# main_4.net
KiCad netlist of a schematic drawn in Altium Designer
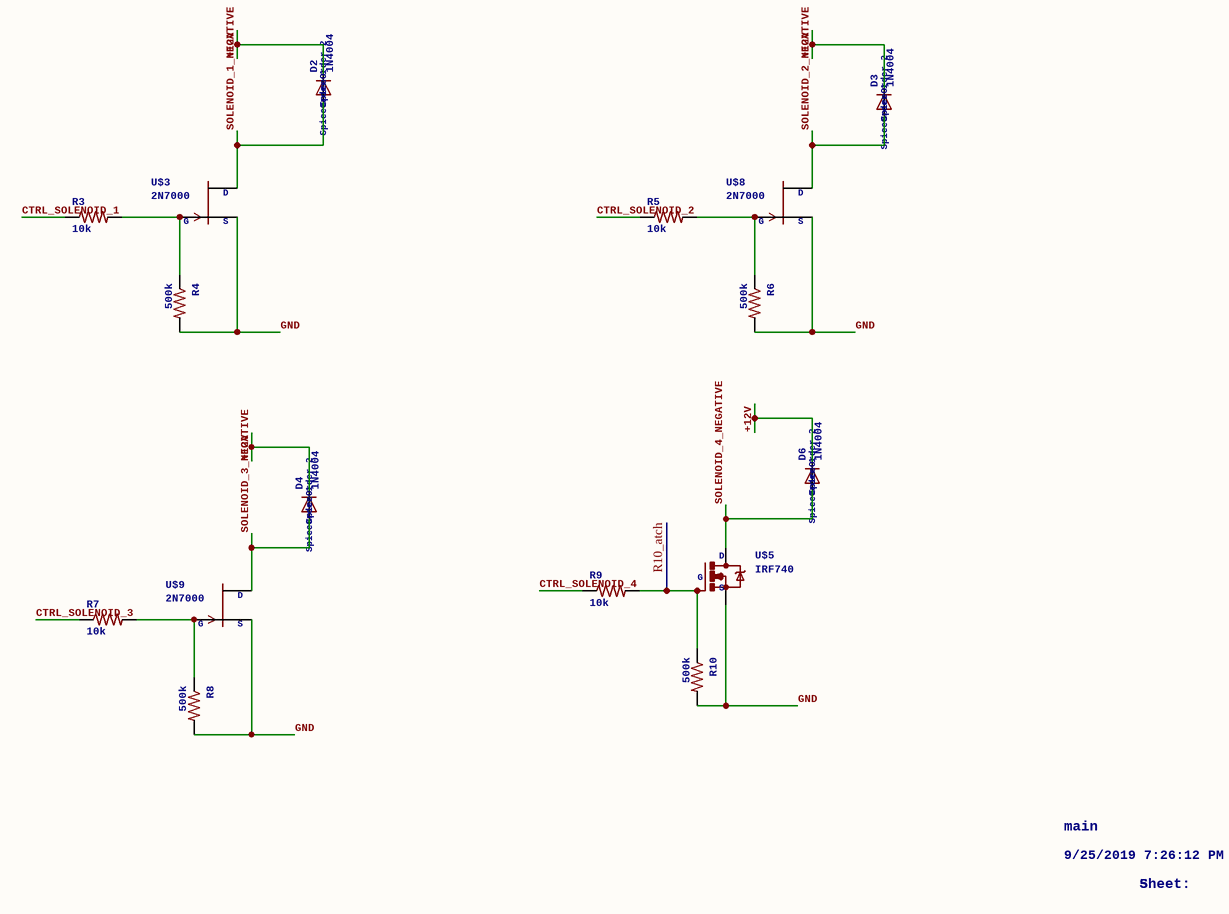
[diagram p0: main_4.SchDoc]

(export (version "E")
  (design (tool "Eeschema 10.0.6"))
  (components
    (comp (ref "D2")
      (value "1N4004")
      (footprint "DO41-10")
      (description "DIODEgeneral purpose rectifier, 1 A")
      (fields (field (name "SPICEORDER1") "SpiceOrder 1") (field (name "SPICEORDER2") "SpiceOrder 2"))
      (libsource (lib "diode") (part "1N4004"))
    )
    (comp (ref "D3")
      (value "1N4004")
      (footprint "DO41-10")
      (description "DIODEgeneral purpose rectifier, 1 A")
      (fields (field (name "SPICEORDER1") "SpiceOrder 1") (field (name "SPICEORDER2") "SpiceOrder 2"))
      (libsource (lib "diode") (part "1N4004"))
    )
    (comp (ref "D4")
      (value "1N4004")
      (footprint "DO41-10")
      (description "DIODEgeneral purpose rectifier, 1 A")
      (fields (field (name "SPICEORDER1") "SpiceOrder 1") (field (name "SPICEORDER2") "SpiceOrder 2"))
      (libsource (lib "diode") (part "1N4004"))
    )
    (comp (ref "D6")
      (value "1N4004")
      (footprint "DO41-10")
      (description "DIODEgeneral purpose rectifier, 1 A")
      (fields (field (name "SPICEORDER1") "SpiceOrder 1") (field (name "SPICEORDER2") "SpiceOrder 2"))
      (libsource (lib "diode") (part "1N4004"))
    )
    (comp (ref "R3")
      (value "10k")
      (footprint "R0805")
      (description "RESISTOR, American symbol")
      (libsource (lib "rcl") (part "R-US_R0805"))
    )
    (comp (ref "R4")
      (value "500k")
      (footprint "R0805")
      (description "RESISTOR, American symbol")
      (libsource (lib "rcl") (part "R-US_R0805"))
    )
    (comp (ref "R5")
      (value "10k")
      (footprint "R0805")
      (description "RESISTOR, American symbol")
      (libsource (lib "rcl") (part "R-US_R0805"))
    )
    (comp (ref "R6")
      (value "500k")
      (footprint "R0805")
      (description "RESISTOR, American symbol")
      (libsource (lib "rcl") (part "R-US_R0805"))
    )
    (comp (ref "R7")
      (value "10k")
      (footprint "R0805")
      (description "RESISTOR, American symbol")
      (libsource (lib "rcl") (part "R-US_R0805"))
    )
    (comp (ref "R8")
      (value "500k")
      (footprint "R0805")
      (description "RESISTOR, American symbol")
      (libsource (lib "rcl") (part "R-US_R0805"))
    )
    (comp (ref "R9")
      (value "10k")
      (footprint "R0805")
      (description "RESISTOR, American symbol")
      (libsource (lib "rcl") (part "R-US_R0805"))
    )
    (comp (ref "R10")
      (value "500k")
      (footprint "R0805")
      (description "RESISTOR, American symbol")
      (libsource (lib "rcl") (part "R-US_R0805"))
    )
    (comp (ref "U$3")
      (value "2N7000")
      (footprint "SOT23")
      (fields
        (field (name "D") "D")
        (field (name "S") "S")
        (field (name "G") "G")
        (field (name "LIBRARYNAME") "transistor-fet-extra")
      )
      (libsource (lib "transistor-fet-extra") (part "2N7000"))
    )
    (comp (ref "U$5")
      (value "IRF740")
      (footprint "TO220BV")
      (description "N-CHANNEL MOS FET")
      (fields (field (name "D") "D") (field (name "S") "S") (field (name "G") "G"))
      (libsource (lib "transistor-power") (part "IRF740"))
    )
    (comp (ref "U$8")
      (value "2N7000")
      (footprint "SOT23")
      (fields
        (field (name "D") "D")
        (field (name "S") "S")
        (field (name "G") "G")
        (field (name "LIBRARYNAME") "transistor-fet-extra")
      )
      (libsource (lib "transistor-fet-extra") (part "2N7000"))
    )
    (comp (ref "U$9")
      (value "2N7000")
      (footprint "SOT23")
      (fields
        (field (name "D") "D")
        (field (name "S") "S")
        (field (name "G") "G")
        (field (name "LIBRARYNAME") "transistor-fet-extra")
      )
      (libsource (lib "transistor-fet-extra") (part "2N7000"))
    )
  )
  (nets
    (net (code "1") (name "/+12V") (class "Default")
      (node (ref "D2") (pin "C") (pinfunction "C_C") (pintype "passive"))
      (node (ref "D3") (pin "C") (pinfunction "C_C") (pintype "passive"))
      (node (ref "D4") (pin "C") (pinfunction "C_C") (pintype "passive"))
      (node (ref "D6") (pin "C") (pinfunction "C_C") (pintype "passive"))
    )
    (net (code "2") (name "/CTRL_SOLENOID_1") (class "Default")
      (node (ref "R3") (pin "1") (pinfunction "1_1") (pintype "passive"))
    )
    (net (code "3") (name "/CTRL_SOLENOID_2") (class "Default")
      (node (ref "R5") (pin "1") (pinfunction "1_1") (pintype "passive"))
    )
    (net (code "4") (name "/CTRL_SOLENOID_3") (class "Default")
      (node (ref "R7") (pin "1") (pinfunction "1_1") (pintype "passive"))
    )
    (net (code "5") (name "/CTRL_SOLENOID_4") (class "Default")
      (node (ref "R9") (pin "1") (pinfunction "1_1") (pintype "passive"))
    )
    (net (code "6") (name "/GND") (class "Default")
      (node (ref "R10") (pin "2") (pinfunction "2_2") (pintype "passive"))
      (node (ref "R4") (pin "2") (pinfunction "2_2") (pintype "passive"))
      (node (ref "R6") (pin "2") (pinfunction "2_2") (pintype "passive"))
      (node (ref "R8") (pin "2") (pinfunction "2_2") (pintype "passive"))
      (node (ref "U$3") (pin "2") (pinfunction "S_2") (pintype "passive"))
      (node (ref "U$5") (pin "S") (pinfunction "S_S") (pintype "passive"))
      (node (ref "U$8") (pin "2") (pinfunction "S_2") (pintype "passive"))
      (node (ref "U$9") (pin "2") (pinfunction "S_2") (pintype "passive"))
    )
    (net (code "7") (name "/R10_atch") (class "Default")
      (node (ref "R10") (pin "1") (pinfunction "1_1") (pintype "passive"))
      (node (ref "R9") (pin "2") (pinfunction "2_2") (pintype "passive"))
      (node (ref "U$5") (pin "G") (pinfunction "G_G") (pintype "passive"))
    )
    (net (code "8") (name "/SOLENOID_1_NEGATIVE") (class "Default")
      (node (ref "D2") (pin "A") (pinfunction "A_A") (pintype "passive"))
      (node (ref "U$3") (pin "3") (pinfunction "D_3") (pintype "passive"))
    )
    (net (code "9") (name "/SOLENOID_2_NEGATIVE") (class "Default")
      (node (ref "D3") (pin "A") (pinfunction "A_A") (pintype "passive"))
      (node (ref "U$8") (pin "3") (pinfunction "D_3") (pintype "passive"))
    )
    (net (code "10") (name "/SOLENOID_3_NEGATIVE") (class "Default")
      (node (ref "D4") (pin "A") (pinfunction "A_A") (pintype "passive"))
      (node (ref "U$9") (pin "3") (pinfunction "D_3") (pintype "passive"))
    )
    (net (code "11") (name "/SOLENOID_4_NEGATIVE") (class "Default")
      (node (ref "D6") (pin "A") (pinfunction "A_A") (pintype "passive"))
      (node (ref "U$5") (pin "D") (pinfunction "D_D") (pintype "passive"))
    )
    (net (code "12") (name "Net-(U$3-G)") (class "Default")
      (node (ref "R3") (pin "2") (pinfunction "2_2") (pintype "passive"))
      (node (ref "R4") (pin "1") (pinfunction "1_1") (pintype "passive"))
      (node (ref "U$3") (pin "1") (pinfunction "G_1") (pintype "passive"))
    )
    (net (code "13") (name "Net-(U$8-G)") (class "Default")
      (node (ref "R5") (pin "2") (pinfunction "2_2") (pintype "passive"))
      (node (ref "R6") (pin "1") (pinfunction "1_1") (pintype "passive"))
      (node (ref "U$8") (pin "1") (pinfunction "G_1") (pintype "passive"))
    )
    (net (code "14") (name "Net-(U$9-G)") (class "Default")
      (node (ref "R7") (pin "2") (pinfunction "2_2") (pintype "passive"))
      (node (ref "R8") (pin "1") (pinfunction "1_1") (pintype "passive"))
      (node (ref "U$9") (pin "1") (pinfunction "G_1") (pintype "passive"))
    )
  )
)
